# 7_RK3588_DDR_Controler.net
KiCad netlist of a schematic drawn in Altium Designer
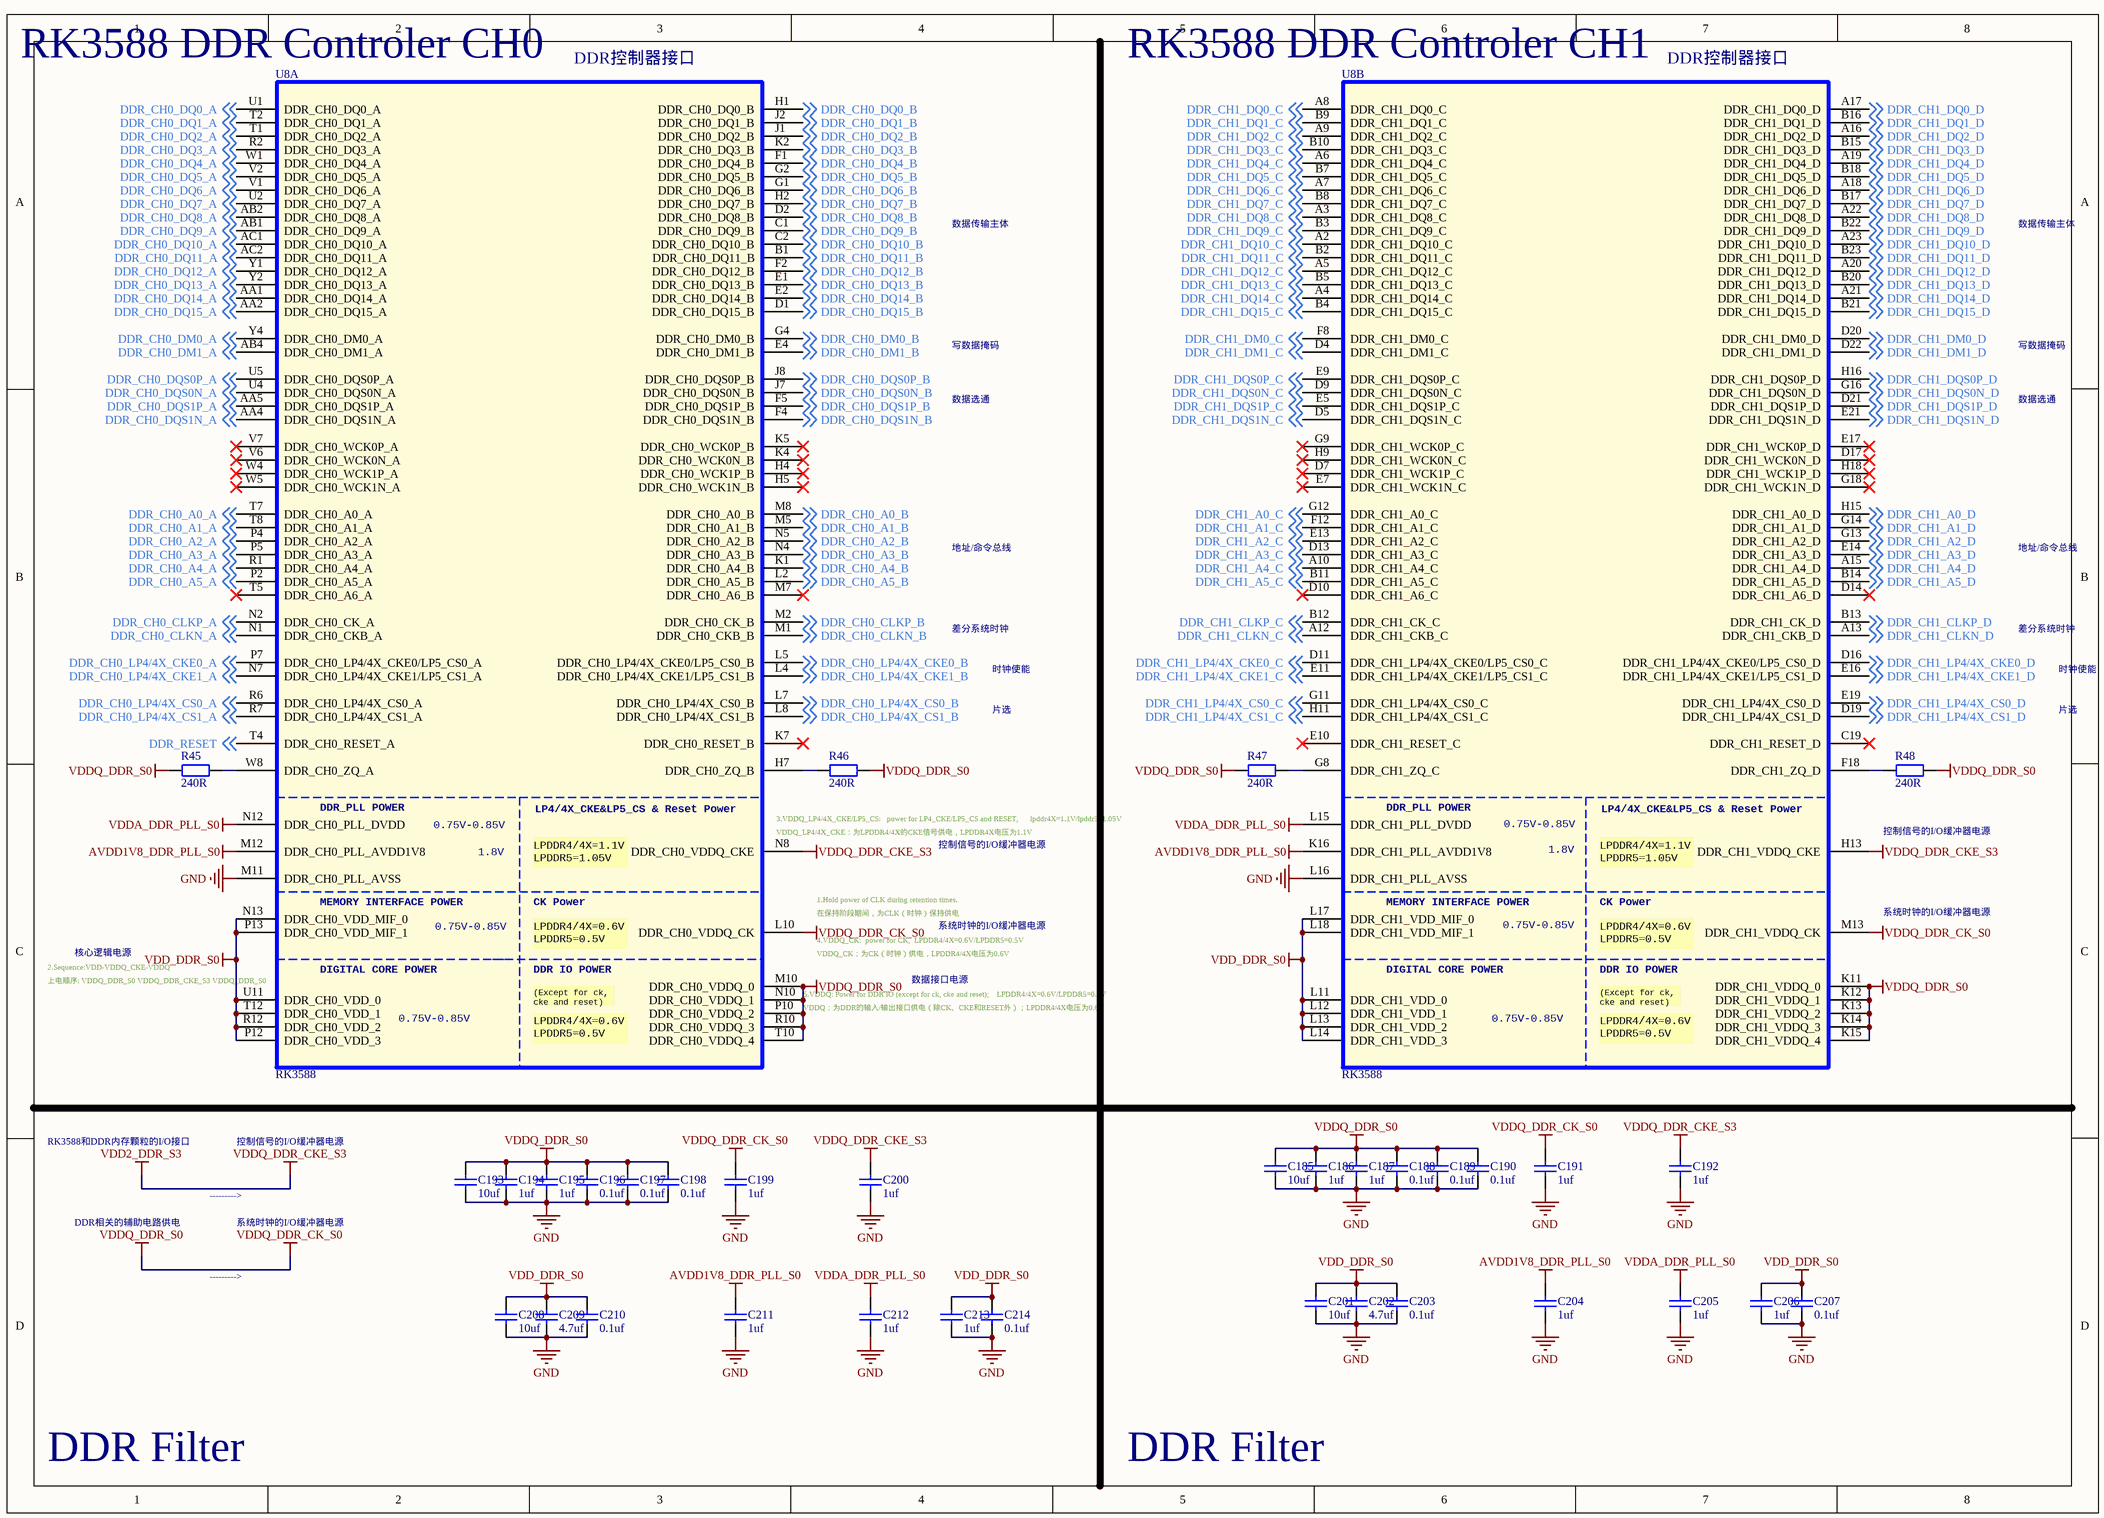
[diagram p0: 7.RK3588_DDR_Controler.SchDoc]

(export (version "E")
  (design (tool "Eeschema 10.0.6"))
  (components
    (comp (ref "C185")
      (value "10uf")
      (footprint "0.PCB1:C0402_L")
      (description "贴片电容/MLCC电容")
      (libsource (lib "RK3588") (part "C"))
    )
    (comp (ref "C186")
      (value "1uf")
      (footprint "0.PCB1:C0201_L")
      (description "贴片电容/MLCC电容")
      (libsource (lib "RK3588") (part "C"))
    )
    (comp (ref "C187")
      (value "1uf")
      (footprint "0.PCB1:C0201_L")
      (description "贴片电容/MLCC电容")
      (libsource (lib "RK3588") (part "C"))
    )
    (comp (ref "C188")
      (value "0.1uf")
      (footprint "0.PCB1:C0201_L")
      (description "贴片电容/MLCC电容")
      (libsource (lib "RK3588") (part "C"))
    )
    (comp (ref "C189")
      (value "0.1uf")
      (footprint "0.PCB1:C0201_L")
      (description "贴片电容/MLCC电容")
      (libsource (lib "RK3588") (part "C"))
    )
    (comp (ref "C190")
      (value "0.1uf")
      (footprint "0.PCB1:C0201_L")
      (description "贴片电容/MLCC电容")
      (libsource (lib "RK3588") (part "C"))
    )
    (comp (ref "C191")
      (value "1uf")
      (footprint "0.PCB1:C0201_L")
      (description "贴片电容/MLCC电容")
      (libsource (lib "RK3588") (part "C"))
    )
    (comp (ref "C192")
      (value "1uf")
      (footprint "0.PCB1:C0201_L")
      (description "贴片电容/MLCC电容")
      (libsource (lib "RK3588") (part "C"))
    )
    (comp (ref "C193")
      (value "10uf")
      (footprint "0.PCB1:C0402_L")
      (description "贴片电容/MLCC电容")
      (libsource (lib "RK3588") (part "C"))
    )
    (comp (ref "C194")
      (value "1uf")
      (footprint "0.PCB1:C0201_L")
      (description "贴片电容/MLCC电容")
      (libsource (lib "RK3588") (part "C"))
    )
    (comp (ref "C195")
      (value "1uf")
      (footprint "0.PCB1:C0201_L")
      (description "贴片电容/MLCC电容")
      (libsource (lib "RK3588") (part "C"))
    )
    (comp (ref "C196")
      (value "0.1uf")
      (footprint "0.PCB1:C0201_L")
      (description "贴片电容/MLCC电容")
      (libsource (lib "RK3588") (part "C"))
    )
    (comp (ref "C197")
      (value "0.1uf")
      (footprint "0.PCB1:C0201_L")
      (description "贴片电容/MLCC电容")
      (libsource (lib "RK3588") (part "C"))
    )
    (comp (ref "C198")
      (value "0.1uf")
      (footprint "0.PCB1:C0201_L")
      (description "贴片电容/MLCC电容")
      (libsource (lib "RK3588") (part "C"))
    )
    (comp (ref "C199")
      (value "1uf")
      (footprint "0.PCB1:C0201_L")
      (description "贴片电容/MLCC电容")
      (libsource (lib "RK3588") (part "C"))
    )
    (comp (ref "C200")
      (value "1uf")
      (footprint "0.PCB1:C0201_L")
      (description "贴片电容/MLCC电容")
      (libsource (lib "RK3588") (part "C"))
    )
    (comp (ref "C201")
      (value "10uf")
      (footprint "0.PCB1:C0402_L")
      (description "贴片电容/MLCC电容")
      (libsource (lib "RK3588") (part "C"))
    )
    (comp (ref "C202")
      (value "4.7uf")
      (footprint "0.PCB1:C0201_L")
      (description "贴片电容/MLCC电容")
      (libsource (lib "RK3588") (part "C"))
    )
    (comp (ref "C203")
      (value "0.1uf")
      (footprint "0.PCB1:C0201_L")
      (description "贴片电容/MLCC电容")
      (libsource (lib "RK3588") (part "C"))
    )
    (comp (ref "C204")
      (value "1uf")
      (footprint "0.PCB1:C0201_L")
      (description "贴片电容/MLCC电容")
      (libsource (lib "RK3588") (part "C"))
    )
    (comp (ref "C205")
      (value "1uf")
      (footprint "0.PCB1:C0201_L")
      (description "贴片电容/MLCC电容")
      (libsource (lib "RK3588") (part "C"))
    )
    (comp (ref "C206")
      (value "1uf")
      (footprint "0.PCB1:C0201_L")
      (description "贴片电容/MLCC电容")
      (libsource (lib "RK3588") (part "C"))
    )
    (comp (ref "C207")
      (value "0.1uf")
      (footprint "0.PCB1:C0201_L")
      (description "贴片电容/MLCC电容")
      (libsource (lib "RK3588") (part "C"))
    )
    (comp (ref "C208")
      (value "10uf")
      (footprint "0.PCB1:C0201_L")
      (description "贴片电容/MLCC电容")
      (libsource (lib "RK3588") (part "C"))
    )
    (comp (ref "C209")
      (value "4.7uf")
      (footprint "0.PCB1:C0201_L")
      (description "贴片电容/MLCC电容")
      (libsource (lib "RK3588") (part "C"))
    )
    (comp (ref "C210")
      (value "0.1uf")
      (footprint "0.PCB1:C0201_L")
      (description "贴片电容/MLCC电容")
      (libsource (lib "RK3588") (part "C"))
    )
    (comp (ref "C211")
      (value "1uf")
      (footprint "0.PCB1:C0201_L")
      (description "贴片电容/MLCC电容")
      (libsource (lib "RK3588") (part "C"))
    )
    (comp (ref "C212")
      (value "1uf")
      (footprint "0.PCB1:C0201_L")
      (description "贴片电容/MLCC电容")
      (libsource (lib "RK3588") (part "C"))
    )
    (comp (ref "C213")
      (value "1uf")
      (footprint "0.PCB1:C0201_L")
      (description "贴片电容/MLCC电容")
      (libsource (lib "RK3588") (part "C"))
    )
    (comp (ref "C214")
      (value "0.1uf")
      (footprint "0.PCB1:C0201_L")
      (description "贴片电容/MLCC电容")
      (libsource (lib "RK3588") (part "C"))
    )
    (comp (ref "R45")
      (value "240R")
      (footprint "0.PCB1:R0201_L")
      (description "贴片电阻")
      (libsource (lib "RK3588") (part "R"))
    )
    (comp (ref "R46")
      (value "240R")
      (footprint "0.PCB1:R0201_L")
      (description "贴片电阻")
      (libsource (lib "RK3588") (part "R"))
    )
    (comp (ref "R47")
      (value "240R")
      (footprint "0.PCB1:R0201_L")
      (description "贴片电阻")
      (libsource (lib "RK3588") (part "R"))
    )
    (comp (ref "R48")
      (value "240R")
      (footprint "0.PCB1:R0201_L")
      (description "贴片电阻")
      (libsource (lib "RK3588") (part "R"))
    )
    (comp (ref "U8")
      (value "RK3588")
      (footprint "0.PCB1:BGA1088_23R00X23R00X2R00")
      (description "ROCKCHIP SOC")
      (libsource (lib "RK3588") (part "SOC_RK3588"))
    )
  )
  (nets
    (net (code "1") (name "AVDD1V8_DDR_PLL_S0") (class "Default")
      (node (ref "C204") (pin "2") (pinfunction "2_2") (pintype "passive"))
      (node (ref "C211") (pin "2") (pinfunction "2_2") (pintype "passive"))
      (node (ref "U8") (pin "K16") (pinfunction "DDR_CH1_PLL_AVDD1V8_K16") (pintype "power_in"))
      (node (ref "U8") (pin "M12") (pinfunction "DDR_CH0_PLL_AVDD1V8_M12") (pintype "power_in"))
    )
    (net (code "2") (name "DDR_CH0_A0_A") (class "Default")
      (node (ref "U8") (pin "T7") (pinfunction "DDR_CH0_A0_A_T7") (pintype "passive"))
    )
    (net (code "3") (name "DDR_CH0_A0_B") (class "Default")
      (node (ref "U8") (pin "M8") (pinfunction "DDR_CH0_A0_B_M8") (pintype "passive"))
    )
    (net (code "4") (name "DDR_CH0_A1_A") (class "Default")
      (node (ref "U8") (pin "T8") (pinfunction "DDR_CH0_A1_A_T8") (pintype "passive"))
    )
    (net (code "5") (name "DDR_CH0_A1_B") (class "Default")
      (node (ref "U8") (pin "M5") (pinfunction "DDR_CH0_A1_B_M5") (pintype "passive"))
    )
    (net (code "6") (name "DDR_CH0_A2_A") (class "Default")
      (node (ref "U8") (pin "P4") (pinfunction "DDR_CH0_A2_A_P4") (pintype "passive"))
    )
    (net (code "7") (name "DDR_CH0_A2_B") (class "Default")
      (node (ref "U8") (pin "N5") (pinfunction "DDR_CH0_A2_B_N5") (pintype "passive"))
    )
    (net (code "8") (name "DDR_CH0_A3_A") (class "Default")
      (node (ref "U8") (pin "P5") (pinfunction "DDR_CH0_A3_A_P5") (pintype "passive"))
    )
    (net (code "9") (name "DDR_CH0_A3_B") (class "Default")
      (node (ref "U8") (pin "N4") (pinfunction "DDR_CH0_A3_B_N4") (pintype "passive"))
    )
    (net (code "10") (name "DDR_CH0_A4_A") (class "Default")
      (node (ref "U8") (pin "R1") (pinfunction "DDR_CH0_A4_A_R1") (pintype "passive"))
    )
    (net (code "11") (name "DDR_CH0_A4_B") (class "Default")
      (node (ref "U8") (pin "K1") (pinfunction "DDR_CH0_A4_B_K1") (pintype "passive"))
    )
    (net (code "12") (name "DDR_CH0_A5_A") (class "Default")
      (node (ref "U8") (pin "P2") (pinfunction "DDR_CH0_A5_A_P2") (pintype "passive"))
    )
    (net (code "13") (name "DDR_CH0_A5_B") (class "Default")
      (node (ref "U8") (pin "L2") (pinfunction "DDR_CH0_A5_B_L2") (pintype "passive"))
    )
    (net (code "14") (name "DDR_CH0_CLKN_A") (class "Default")
      (node (ref "U8") (pin "N1") (pinfunction "DDR_CH0_CKB_A_N1") (pintype "passive"))
    )
    (net (code "15") (name "DDR_CH0_CLKN_B") (class "Default")
      (node (ref "U8") (pin "M1") (pinfunction "DDR_CH0_CKB_B_M1") (pintype "passive"))
    )
    (net (code "16") (name "DDR_CH0_CLKP_A") (class "Default")
      (node (ref "U8") (pin "N2") (pinfunction "DDR_CH0_CK_A_N2") (pintype "passive"))
    )
    (net (code "17") (name "DDR_CH0_CLKP_B") (class "Default")
      (node (ref "U8") (pin "M2") (pinfunction "DDR_CH0_CK_B_M2") (pintype "passive"))
    )
    (net (code "18") (name "DDR_CH0_DM0_A") (class "Default")
      (node (ref "U8") (pin "Y4") (pinfunction "DDR_CH0_DM0_A_Y4") (pintype "passive"))
    )
    (net (code "19") (name "DDR_CH0_DM0_B") (class "Default")
      (node (ref "U8") (pin "G4") (pinfunction "DDR_CH0_DM0_B_G4") (pintype "passive"))
    )
    (net (code "20") (name "DDR_CH0_DM1_A") (class "Default")
      (node (ref "U8") (pin "AB4") (pinfunction "DDR_CH0_DM1_A_AB4") (pintype "passive"))
    )
    (net (code "21") (name "DDR_CH0_DM1_B") (class "Default")
      (node (ref "U8") (pin "E4") (pinfunction "DDR_CH0_DM1_B_E4") (pintype "passive"))
    )
    (net (code "22") (name "DDR_CH0_DQ0_A") (class "Default")
      (node (ref "U8") (pin "U1") (pinfunction "DDR_CH0_DQ0_A_U1") (pintype "passive"))
    )
    (net (code "23") (name "DDR_CH0_DQ0_B") (class "Default")
      (node (ref "U8") (pin "H1") (pinfunction "DDR_CH0_DQ0_B_H1") (pintype "passive"))
    )
    (net (code "24") (name "DDR_CH0_DQ1_A") (class "Default")
      (node (ref "U8") (pin "T2") (pinfunction "DDR_CH0_DQ1_A_T2") (pintype "passive"))
    )
    (net (code "25") (name "DDR_CH0_DQ1_B") (class "Default")
      (node (ref "U8") (pin "J2") (pinfunction "DDR_CH0_DQ1_B_J2") (pintype "passive"))
    )
    (net (code "26") (name "DDR_CH0_DQ2_A") (class "Default")
      (node (ref "U8") (pin "T1") (pinfunction "DDR_CH0_DQ2_A_T1") (pintype "passive"))
    )
    (net (code "27") (name "DDR_CH0_DQ2_B") (class "Default")
      (node (ref "U8") (pin "J1") (pinfunction "DDR_CH0_DQ2_B_J1") (pintype "passive"))
    )
    (net (code "28") (name "DDR_CH0_DQ3_A") (class "Default")
      (node (ref "U8") (pin "R2") (pinfunction "DDR_CH0_DQ3_A_R2") (pintype "passive"))
    )
    (net (code "29") (name "DDR_CH0_DQ3_B") (class "Default")
      (node (ref "U8") (pin "K2") (pinfunction "DDR_CH0_DQ3_B_K2") (pintype "passive"))
    )
    (net (code "30") (name "DDR_CH0_DQ4_A") (class "Default")
      (node (ref "U8") (pin "W1") (pinfunction "DDR_CH0_DQ4_A_W1") (pintype "passive"))
    )
    (net (code "31") (name "DDR_CH0_DQ4_B") (class "Default")
      (node (ref "U8") (pin "F1") (pinfunction "DDR_CH0_DQ4_B_F1") (pintype "passive"))
    )
    (net (code "32") (name "DDR_CH0_DQ5_A") (class "Default")
      (node (ref "U8") (pin "V2") (pinfunction "DDR_CH0_DQ5_A_V2") (pintype "passive"))
    )
    (net (code "33") (name "DDR_CH0_DQ5_B") (class "Default")
      (node (ref "U8") (pin "G2") (pinfunction "DDR_CH0_DQ5_B_G2") (pintype "passive"))
    )
    (net (code "34") (name "DDR_CH0_DQ6_A") (class "Default")
      (node (ref "U8") (pin "V1") (pinfunction "DDR_CH0_DQ6_A_V1") (pintype "passive"))
    )
    (net (code "35") (name "DDR_CH0_DQ6_B") (class "Default")
      (node (ref "U8") (pin "G1") (pinfunction "DDR_CH0_DQ6_B_G1") (pintype "passive"))
    )
    (net (code "36") (name "DDR_CH0_DQ7_A") (class "Default")
      (node (ref "U8") (pin "U2") (pinfunction "DDR_CH0_DQ7_A_U2") (pintype "passive"))
    )
    (net (code "37") (name "DDR_CH0_DQ7_B") (class "Default")
      (node (ref "U8") (pin "H2") (pinfunction "DDR_CH0_DQ7_B_H2") (pintype "passive"))
    )
    (net (code "38") (name "DDR_CH0_DQ8_A") (class "Default")
      (node (ref "U8") (pin "AB2") (pinfunction "DDR_CH0_DQ8_A_AB2") (pintype "passive"))
    )
    (net (code "39") (name "DDR_CH0_DQ8_B") (class "Default")
      (node (ref "U8") (pin "D2") (pinfunction "DDR_CH0_DQ8_B_D2") (pintype "passive"))
    )
    (net (code "40") (name "DDR_CH0_DQ9_A") (class "Default")
      (node (ref "U8") (pin "AB1") (pinfunction "DDR_CH0_DQ9_A_AB1") (pintype "passive"))
    )
    (net (code "41") (name "DDR_CH0_DQ9_B") (class "Default")
      (node (ref "U8") (pin "C1") (pinfunction "DDR_CH0_DQ9_B_C1") (pintype "passive"))
    )
    (net (code "42") (name "DDR_CH0_DQ10_A") (class "Default")
      (node (ref "U8") (pin "AC1") (pinfunction "DDR_CH0_DQ10_A_AC1") (pintype "passive"))
    )
    (net (code "43") (name "DDR_CH0_DQ10_B") (class "Default")
      (node (ref "U8") (pin "C2") (pinfunction "DDR_CH0_DQ10_B_C2") (pintype "passive"))
    )
    (net (code "44") (name "DDR_CH0_DQ11_A") (class "Default")
      (node (ref "U8") (pin "AC2") (pinfunction "DDR_CH0_DQ11_A_AC2") (pintype "passive"))
    )
    (net (code "45") (name "DDR_CH0_DQ11_B") (class "Default")
      (node (ref "U8") (pin "B1") (pinfunction "DDR_CH0_DQ11_B_B1") (pintype "passive"))
    )
    (net (code "46") (name "DDR_CH0_DQ12_A") (class "Default")
      (node (ref "U8") (pin "Y1") (pinfunction "DDR_CH0_DQ12_A_Y1") (pintype "passive"))
    )
    (net (code "47") (name "DDR_CH0_DQ12_B") (class "Default")
      (node (ref "U8") (pin "F2") (pinfunction "DDR_CH0_DQ12_B_F2") (pintype "passive"))
    )
    (net (code "48") (name "DDR_CH0_DQ13_A") (class "Default")
      (node (ref "U8") (pin "Y2") (pinfunction "DDR_CH0_DQ13_A_Y2") (pintype "passive"))
    )
    (net (code "49") (name "DDR_CH0_DQ13_B") (class "Default")
      (node (ref "U8") (pin "E1") (pinfunction "DDR_CH0_DQ13_B_E1") (pintype "passive"))
    )
    (net (code "50") (name "DDR_CH0_DQ14_A") (class "Default")
      (node (ref "U8") (pin "AA1") (pinfunction "DDR_CH0_DQ14_A_AA1") (pintype "passive"))
    )
    (net (code "51") (name "DDR_CH0_DQ14_B") (class "Default")
      (node (ref "U8") (pin "E2") (pinfunction "DDR_CH0_DQ14_B_E2") (pintype "passive"))
    )
    (net (code "52") (name "DDR_CH0_DQ15_A") (class "Default")
      (node (ref "U8") (pin "AA2") (pinfunction "DDR_CH0_DQ15_A_AA2") (pintype "passive"))
    )
    (net (code "53") (name "DDR_CH0_DQ15_B") (class "Default")
      (node (ref "U8") (pin "D1") (pinfunction "DDR_CH0_DQ15_B_D1") (pintype "passive"))
    )
    (net (code "54") (name "DDR_CH0_DQS0N_A") (class "Default")
      (node (ref "U8") (pin "U4") (pinfunction "DDR_CH0_DQS0N_A_U4") (pintype "passive"))
    )
    (net (code "55") (name "DDR_CH0_DQS0N_B") (class "Default")
      (node (ref "U8") (pin "J7") (pinfunction "DDR_CH0_DQS0N_B_J7") (pintype "passive"))
    )
    (net (code "56") (name "DDR_CH0_DQS0P_A") (class "Default")
      (node (ref "U8") (pin "U5") (pinfunction "DDR_CH0_DQS0P_A_U5") (pintype "passive"))
    )
    (net (code "57") (name "DDR_CH0_DQS0P_B") (class "Default")
      (node (ref "U8") (pin "J8") (pinfunction "DDR_CH0_DQS0P_B_J8") (pintype "passive"))
    )
    (net (code "58") (name "DDR_CH0_DQS1N_A") (class "Default")
      (node (ref "U8") (pin "AA4") (pinfunction "DDR_CH0_DQS1N_A_AA4") (pintype "passive"))
    )
    (net (code "59") (name "DDR_CH0_DQS1N_B") (class "Default")
      (node (ref "U8") (pin "F4") (pinfunction "DDR_CH0_DQS1N_B_F4") (pintype "passive"))
    )
    (net (code "60") (name "DDR_CH0_DQS1P_A") (class "Default")
      (node (ref "U8") (pin "AA5") (pinfunction "DDR_CH0_DQS1P_A_AA5") (pintype "passive"))
    )
    (net (code "61") (name "DDR_CH0_DQS1P_B") (class "Default")
      (node (ref "U8") (pin "F5") (pinfunction "DDR_CH0_DQS1P_B_F5") (pintype "passive"))
    )
    (net (code "62") (name "DDR_CH0_LP4{slash}4X_CKE0_A") (class "Default")
      (node (ref "U8") (pin "P7") (pinfunction "DDR_CH0_LP4/4X_CKE0/LP5_CS0_A_P7") (pintype "passive"))
    )
    (net (code "63") (name "DDR_CH0_LP4{slash}4X_CKE0_B") (class "Default")
      (node (ref "U8") (pin "L5") (pinfunction "DDR_CH0_LP4/4X_CKE0/LP5_CS0_B_L5") (pintype "passive"))
    )
    (net (code "64") (name "DDR_CH0_LP4{slash}4X_CKE1_A") (class "Default")
      (node (ref "U8") (pin "N7") (pinfunction "DDR_CH0_LP4/4X_CKE1/LP5_CS1_A_N7") (pintype "passive"))
    )
    (net (code "65") (name "DDR_CH0_LP4{slash}4X_CKE1_B") (class "Default")
      (node (ref "U8") (pin "L4") (pinfunction "DDR_CH0_LP4/4X_CKE1/LP5_CS1_B_L4") (pintype "passive"))
    )
    (net (code "66") (name "DDR_CH0_LP4{slash}4X_CS0_A") (class "Default")
      (node (ref "U8") (pin "R6") (pinfunction "DDR_CH0_LP4/4X_CS0_A_R6") (pintype "passive"))
    )
    (net (code "67") (name "DDR_CH0_LP4{slash}4X_CS0_B") (class "Default")
      (node (ref "U8") (pin "L7") (pinfunction "DDR_CH0_LP4/4X_CS0_B_L7") (pintype "passive"))
    )
    (net (code "68") (name "DDR_CH0_LP4{slash}4X_CS1_A") (class "Default")
      (node (ref "U8") (pin "R7") (pinfunction "DDR_CH0_LP4/4X_CS1_A_R7") (pintype "passive"))
    )
    (net (code "69") (name "DDR_CH0_LP4{slash}4X_CS1_B") (class "Default")
      (node (ref "U8") (pin "L8") (pinfunction "DDR_CH0_LP4/4X_CS1_B_L8") (pintype "passive"))
    )
    (net (code "70") (name "DDR_CH1_A0_C") (class "Default")
      (node (ref "U8") (pin "G12") (pinfunction "DDR_CH1_A0_C_G12") (pintype "passive"))
    )
    (net (code "71") (name "DDR_CH1_A0_D") (class "Default")
      (node (ref "U8") (pin "H15") (pinfunction "DDR_CH1_A0_D_H15") (pintype "passive"))
    )
    (net (code "72") (name "DDR_CH1_A1_C") (class "Default")
      (node (ref "U8") (pin "F12") (pinfunction "DDR_CH1_A1_C_F12") (pintype "passive"))
    )
    (net (code "73") (name "DDR_CH1_A1_D") (class "Default")
      (node (ref "U8") (pin "G14") (pinfunction "DDR_CH1_A1_D_G14") (pintype "passive"))
    )
    (net (code "74") (name "DDR_CH1_A2_C") (class "Default")
      (node (ref "U8") (pin "E13") (pinfunction "DDR_CH1_A2_C_E13") (pintype "passive"))
    )
    (net (code "75") (name "DDR_CH1_A2_D") (class "Default")
      (node (ref "U8") (pin "G13") (pinfunction "DDR_CH1_A2_D_G13") (pintype "passive"))
    )
    (net (code "76") (name "DDR_CH1_A3_C") (class "Default")
      (node (ref "U8") (pin "D13") (pinfunction "DDR_CH1_A3_C_D13") (pintype "passive"))
    )
    (net (code "77") (name "DDR_CH1_A3_D") (class "Default")
      (node (ref "U8") (pin "E14") (pinfunction "DDR_CH1_A3_D_E14") (pintype "passive"))
    )
    (net (code "78") (name "DDR_CH1_A4_C") (class "Default")
      (node (ref "U8") (pin "A10") (pinfunction "DDR_CH1_A4_C_A10") (pintype "passive"))
    )
    (net (code "79") (name "DDR_CH1_A4_D") (class "Default")
      (node (ref "U8") (pin "A15") (pinfunction "DDR_CH1_A4_D_A15") (pintype "passive"))
    )
    (net (code "80") (name "DDR_CH1_A5_C") (class "Default")
      (node (ref "U8") (pin "B11") (pinfunction "DDR_CH1_A5_C_B11") (pintype "passive"))
    )
    (net (code "81") (name "DDR_CH1_A5_D") (class "Default")
      (node (ref "U8") (pin "B14") (pinfunction "DDR_CH1_A5_D_B14") (pintype "passive"))
    )
    (net (code "82") (name "DDR_CH1_CLKN_C") (class "Default")
      (node (ref "U8") (pin "A12") (pinfunction "DDR_CH1_CKB_C_A12") (pintype "passive"))
    )
    (net (code "83") (name "DDR_CH1_CLKN_D") (class "Default")
      (node (ref "U8") (pin "A13") (pinfunction "DDR_CH1_CKB_D_A13") (pintype "passive"))
    )
    (net (code "84") (name "DDR_CH1_CLKP_C") (class "Default")
      (node (ref "U8") (pin "B12") (pinfunction "DDR_CH1_CK_C_B12") (pintype "passive"))
    )
    (net (code "85") (name "DDR_CH1_CLKP_D") (class "Default")
      (node (ref "U8") (pin "B13") (pinfunction "DDR_CH1_CK_D_B13") (pintype "passive"))
    )
    (net (code "86") (name "DDR_CH1_DM0_C") (class "Default")
      (node (ref "U8") (pin "F8") (pinfunction "DDR_CH1_DM0_C_F8") (pintype "passive"))
    )
    (net (code "87") (name "DDR_CH1_DM0_D") (class "Default")
      (node (ref "U8") (pin "D20") (pinfunction "DDR_CH1_DM0_D_D20") (pintype "passive"))
    )
    (net (code "88") (name "DDR_CH1_DM1_C") (class "Default")
      (node (ref "U8") (pin "D4") (pinfunction "DDR_CH1_DM1_C_D4") (pintype "passive"))
    )
    (net (code "89") (name "DDR_CH1_DM1_D") (class "Default")
      (node (ref "U8") (pin "D22") (pinfunction "DDR_CH1_DM1_D_D22") (pintype "passive"))
    )
    (net (code "90") (name "DDR_CH1_DQ0_C") (class "Default")
      (node (ref "U8") (pin "A8") (pinfunction "DDR_CH1_DQ0_C_A8") (pintype "passive"))
    )
    (net (code "91") (name "DDR_CH1_DQ0_D") (class "Default")
      (node (ref "U8") (pin "A17") (pinfunction "DDR_CH1_DQ0_D_A17") (pintype "passive"))
    )
    (net (code "92") (name "DDR_CH1_DQ1_C") (class "Default")
      (node (ref "U8") (pin "B9") (pinfunction "DDR_CH1_DQ1_C_B9") (pintype "passive"))
    )
    (net (code "93") (name "DDR_CH1_DQ1_D") (class "Default")
      (node (ref "U8") (pin "B16") (pinfunction "DDR_CH1_DQ1_D_B16") (pintype "passive"))
    )
    (net (code "94") (name "DDR_CH1_DQ2_C") (class "Default")
      (node (ref "U8") (pin "A9") (pinfunction "DDR_CH1_DQ2_C_A9") (pintype "passive"))
    )
    (net (code "95") (name "DDR_CH1_DQ2_D") (class "Default")
      (node (ref "U8") (pin "A16") (pinfunction "DDR_CH1_DQ2_D_A16") (pintype "passive"))
    )
    (net (code "96") (name "DDR_CH1_DQ3_C") (class "Default")
      (node (ref "U8") (pin "B10") (pinfunction "DDR_CH1_DQ3_C_B10") (pintype "passive"))
    )
    (net (code "97") (name "DDR_CH1_DQ3_D") (class "Default")
      (node (ref "U8") (pin "B15") (pinfunction "DDR_CH1_DQ3_D_B15") (pintype "passive"))
    )
    (net (code "98") (name "DDR_CH1_DQ4_C") (class "Default")
      (node (ref "U8") (pin "A6") (pinfunction "DDR_CH1_DQ4_C_A6") (pintype "passive"))
    )
    (net (code "99") (name "DDR_CH1_DQ4_D") (class "Default")
      (node (ref "U8") (pin "A19") (pinfunction "DDR_CH1_DQ4_D_A19") (pintype "passive"))
    )
    (net (code "100") (name "DDR_CH1_DQ5_C") (class "Default")
      (node (ref "U8") (pin "B7") (pinfunction "DDR_CH1_DQ5_C_B7") (pintype "passive"))
    )
    (net (code "101") (name "DDR_CH1_DQ5_D") (class "Default")
      (node (ref "U8") (pin "B18") (pinfunction "DDR_CH1_DQ5_D_B18") (pintype "passive"))
    )
    (net (code "102") (name "DDR_CH1_DQ6_C") (class "Default")
      (node (ref "U8") (pin "A7") (pinfunction "DDR_CH1_DQ6_C_A7") (pintype "passive"))
    )
    (net (code "103") (name "DDR_CH1_DQ6_D") (class "Default")
      (node (ref "U8") (pin "A18") (pinfunction "DDR_CH1_DQ6_D_A18") (pintype "passive"))
    )
    (net (code "104") (name "DDR_CH1_DQ7_C") (class "Default")
      (node (ref "U8") (pin "B8") (pinfunction "DDR_CH1_DQ7_C_B8") (pintype "passive"))
    )
    (net (code "105") (name "DDR_CH1_DQ7_D") (class "Default")
      (node (ref "U8") (pin "B17") (pinfunction "DDR_CH1_DQ7_D_B17") (pintype "passive"))
    )
    (net (code "106") (name "DDR_CH1_DQ8_C") (class "Default")
      (node (ref "U8") (pin "A3") (pinfunction "DDR_CH1_DQ8_C_A3") (pintype "passive"))
    )
    (net (code "107") (name "DDR_CH1_DQ8_D") (class "Default")
      (node (ref "U8") (pin "A22") (pinfunction "DDR_CH1_DQ8_D_A22") (pintype "passive"))
    )
    (net (code "108") (name "DDR_CH1_DQ9_C") (class "Default")
      (node (ref "U8") (pin "B3") (pinfunction "DDR_CH1_DQ9_C_B3") (pintype "passive"))
    )
    (net (code "109") (name "DDR_CH1_DQ9_D") (class "Default")
      (node (ref "U8") (pin "B22") (pinfunction "DDR_CH1_DQ9_D_B22") (pintype "passive"))
    )
    (net (code "110") (name "DDR_CH1_DQ10_C") (class "Default")
      (node (ref "U8") (pin "A2") (pinfunction "DDR_CH1_DQ10_C_A2") (pintype "passive"))
    )
    (net (code "111") (name "DDR_CH1_DQ10_D") (class "Default")
      (node (ref "U8") (pin "A23") (pinfunction "DDR_CH1_DQ10_D_A23") (pintype "passive"))
    )
    (net (code "112") (name "DDR_CH1_DQ11_C") (class "Default")
      (node (ref "U8") (pin "B2") (pinfunction "DDR_CH1_DQ11_C_B2") (pintype "passive"))
    )
    (net (code "113") (name "DDR_CH1_DQ11_D") (class "Default")
      (node (ref "U8") (pin "B23") (pinfunction "DDR_CH1_DQ11_D_B23") (pintype "passive"))
    )
    (net (code "114") (name "DDR_CH1_DQ12_C") (class "Default")
      (node (ref "U8") (pin "A5") (pinfunction "DDR_CH1_DQ12_C_A5") (pintype "passive"))
    )
    (net (code "115") (name "DDR_CH1_DQ12_D") (class "Default")
      (node (ref "U8") (pin "A20") (pinfunction "DDR_CH1_DQ12_D_A20") (pintype "passive"))
    )
    (net (code "116") (name "DDR_CH1_DQ13_C") (class "Default")
      (node (ref "U8") (pin "B5") (pinfunction "DDR_CH1_DQ13_C_B5") (pintype "passive"))
    )
    (net (code "117") (name "DDR_CH1_DQ13_D") (class "Default")
      (node (ref "U8") (pin "B20") (pinfunction "DDR_CH1_DQ13_D_B20") (pintype "passive"))
    )
    (net (code "118") (name "DDR_CH1_DQ14_C") (class "Default")
      (node (ref "U8") (pin "A4") (pinfunction "DDR_CH1_DQ14_C_A4") (pintype "passive"))
    )
    (net (code "119") (name "DDR_CH1_DQ14_D") (class "Default")
      (node (ref "U8") (pin "A21") (pinfunction "DDR_CH1_DQ14_D_A21") (pintype "passive"))
    )
    (net (code "120") (name "DDR_CH1_DQ15_C") (class "Default")
      (node (ref "U8") (pin "B4") (pinfunction "DDR_CH1_DQ15_C_B4") (pintype "passive"))
    )
    (net (code "121") (name "DDR_CH1_DQ15_D") (class "Default")
      (node (ref "U8") (pin "B21") (pinfunction "DDR_CH1_DQ15_D_B21") (pintype "passive"))
    )
    (net (code "122") (name "DDR_CH1_DQS0N_C") (class "Default")
      (node (ref "U8") (pin "D9") (pinfunction "DDR_CH1_DQS0N_C_D9") (pintype "passive"))
    )
    (net (code "123") (name "DDR_CH1_DQS0N_D") (class "Default")
      (node (ref "U8") (pin "G16") (pinfunction "DDR_CH1_DQS0N_D_G16") (pintype "passive"))
    )
    (net (code "124") (name "DDR_CH1_DQS0P_C") (class "Default")
      (node (ref "U8") (pin "E9") (pinfunction "DDR_CH1_DQS0P_C_E9") (pintype "passive"))
    )
    (net (code "125") (name "DDR_CH1_DQS0P_D") (class "Default")
      (node (ref "U8") (pin "H16") (pinfunction "DDR_CH1_DQS0P_D_H16") (pintype "passive"))
    )
    (net (code "126") (name "DDR_CH1_DQS1N_C") (class "Default")
      (node (ref "U8") (pin "D5") (pinfunction "DDR_CH1_DQS1N_C_D5") (pintype "passive"))
    )
    (net (code "127") (name "DDR_CH1_DQS1N_D") (class "Default")
      (node (ref "U8") (pin "E21") (pinfunction "DDR_CH1_DQS1N_D_E21") (pintype "passive"))
    )
    (net (code "128") (name "DDR_CH1_DQS1P_C") (class "Default")
      (node (ref "U8") (pin "E5") (pinfunction "DDR_CH1_DQS1P_C_E5") (pintype "passive"))
    )
    (net (code "129") (name "DDR_CH1_DQS1P_D") (class "Default")
      (node (ref "U8") (pin "D21") (pinfunction "DDR_CH1_DQS1P_D_D21") (pintype "passive"))
    )
    (net (code "130") (name "DDR_CH1_LP4{slash}4X_CKE0_C") (class "Default")
      (node (ref "U8") (pin "D11") (pinfunction "DDR_CH1_LP4/4X_CKE0/LP5_CS0_C_D11") (pintype "passive"))
    )
    (net (code "131") (name "DDR_CH1_LP4{slash}4X_CKE0_D") (class "Default")
      (node (ref "U8") (pin "D16") (pinfunction "DDR_CH1_LP4/4X_CKE0/LP5_CS0_D_D16") (pintype "passive"))
    )
    (net (code "132") (name "DDR_CH1_LP4{slash}4X_CKE1_C") (class "Default")
      (node (ref "U8") (pin "E11") (pinfunction "DDR_CH1_LP4/4X_CKE1/LP5_CS1_C_E11") (pintype "passive"))
    )
    (net (code "133") (name "DDR_CH1_LP4{slash}4X_CKE1_D") (class "Default")
      (node (ref "U8") (pin "E16") (pinfunction "DDR_CH1_LP4/4X_CKE1/LP5_CS1_D_E16") (pintype "passive"))
    )
    (net (code "134") (name "DDR_CH1_LP4{slash}4X_CS0_C") (class "Default")
      (node (ref "U8") (pin "G11") (pinfunction "DDR_CH1_LP4/4X_CS0_C_G11") (pintype "passive"))
    )
    (net (code "135") (name "DDR_CH1_LP4{slash}4X_CS0_D") (class "Default")
      (node (ref "U8") (pin "E19") (pinfunction "DDR_CH1_LP4/4X_CS0_D_E19") (pintype "passive"))
    )
    (net (code "136") (name "DDR_CH1_LP4{slash}4X_CS1_C") (class "Default")
      (node (ref "U8") (pin "H11") (pinfunction "DDR_CH1_LP4/4X_CS1_C_H11") (pintype "passive"))
    )
    (net (code "137") (name "DDR_CH1_LP4{slash}4X_CS1_D") (class "Default")
      (node (ref "U8") (pin "D19") (pinfunction "DDR_CH1_LP4/4X_CS1_D_D19") (pintype "passive"))
    )
    (net (code "138") (name "DDR_RESET") (class "Default")
      (node (ref "U8") (pin "T4") (pinfunction "DDR_CH0_RESET_A_T4") (pintype "passive"))
    )
    (net (code "139") (name "GND") (class "Default")
      (node (ref "C185") (pin "1") (pinfunction "1_1") (pintype "passive"))
      (node (ref "C186") (pin "1") (pinfunction "1_1") (pintype "passive"))
      (node (ref "C187") (pin "1") (pinfunction "1_1") (pintype "passive"))
      (node (ref "C188") (pin "1") (pinfunction "1_1") (pintype "passive"))
      (node (ref "C189") (pin "1") (pinfunction "1_1") (pintype "passive"))
      (node (ref "C190") (pin "1") (pinfunction "1_1") (pintype "passive"))
      (node (ref "C191") (pin "1") (pinfunction "1_1") (pintype "passive"))
      (node (ref "C192") (pin "1") (pinfunction "1_1") (pintype "passive"))
      (node (ref "C193") (pin "1") (pinfunction "1_1") (pintype "passive"))
      (node (ref "C194") (pin "1") (pinfunction "1_1") (pintype "passive"))
      (node (ref "C195") (pin "1") (pinfunction "1_1") (pintype "passive"))
      (node (ref "C196") (pin "1") (pinfunction "1_1") (pintype "passive"))
      (node (ref "C197") (pin "1") (pinfunction "1_1") (pintype "passive"))
      (node (ref "C198") (pin "1") (pinfunction "1_1") (pintype "passive"))
      (node (ref "C199") (pin "1") (pinfunction "1_1") (pintype "passive"))
      (node (ref "C200") (pin "1") (pinfunction "1_1") (pintype "passive"))
      (node (ref "C201") (pin "1") (pinfunction "1_1") (pintype "passive"))
      (node (ref "C202") (pin "1") (pinfunction "1_1") (pintype "passive"))
      (node (ref "C203") (pin "1") (pinfunction "1_1") (pintype "passive"))
      (node (ref "C204") (pin "1") (pinfunction "1_1") (pintype "passive"))
      (node (ref "C205") (pin "1") (pinfunction "1_1") (pintype "passive"))
      (node (ref "C206") (pin "1") (pinfunction "1_1") (pintype "passive"))
      (node (ref "C207") (pin "1") (pinfunction "1_1") (pintype "passive"))
      (node (ref "C208") (pin "1") (pinfunction "1_1") (pintype "passive"))
      (node (ref "C209") (pin "1") (pinfunction "1_1") (pintype "passive"))
      (node (ref "C210") (pin "1") (pinfunction "1_1") (pintype "passive"))
      (node (ref "C211") (pin "1") (pinfunction "1_1") (pintype "passive"))
      (node (ref "C212") (pin "1") (pinfunction "1_1") (pintype "passive"))
      (node (ref "C213") (pin "1") (pinfunction "1_1") (pintype "passive"))
      (node (ref "C214") (pin "1") (pinfunction "1_1") (pintype "passive"))
      (node (ref "U8") (pin "L16") (pinfunction "DDR_CH1_PLL_AVSS_L16") (pintype "power_in"))
      (node (ref "U8") (pin "M11") (pinfunction "DDR_CH0_PLL_AVSS_M11") (pintype "power_in"))
    )
    (net (code "140") (name "Net-(U8A-DDR_CH0_ZQ_A)") (class "Default")
      (node (ref "R45") (pin "2") (pinfunction "2_2") (pintype "passive"))
      (node (ref "U8") (pin "W8") (pinfunction "DDR_CH0_ZQ_A_W8") (pintype "passive"))
    )
    (net (code "141") (name "Net-(U8A-DDR_CH0_ZQ_B)") (class "Default")
      (node (ref "R46") (pin "2") (pinfunction "2_2") (pintype "passive"))
      (node (ref "U8") (pin "H7") (pinfunction "DDR_CH0_ZQ_B_H7") (pintype "passive"))
    )
    (net (code "142") (name "Net-(U8B-DDR_CH1_ZQ_C)") (class "Default")
      (node (ref "R47") (pin "2") (pinfunction "2_2") (pintype "passive"))
      (node (ref "U8") (pin "G8") (pinfunction "DDR_CH1_ZQ_C_G8") (pintype "passive"))
    )
    (net (code "143") (name "Net-(U8B-DDR_CH1_ZQ_D)") (class "Default")
      (node (ref "R48") (pin "2") (pinfunction "2_2") (pintype "passive"))
      (node (ref "U8") (pin "F18") (pinfunction "DDR_CH1_ZQ_D_F18") (pintype "passive"))
    )
    (net (code "144") (name "VDD2_DDR_S3") (class "Default")
      (node (ref "C192") (pin "2") (pinfunction "2_2") (pintype "passive"))
      (node (ref "C200") (pin "2") (pinfunction "2_2") (pintype "passive"))
      (node (ref "U8") (pin "H13") (pinfunction "DDR_CH1_VDDQ_CKE_H13") (pintype "power_in"))
      (node (ref "U8") (pin "N8") (pinfunction "DDR_CH0_VDDQ_CKE_N8") (pintype "power_in"))
    )
    (net (code "145") (name "VDDA_DDR_PLL_S0") (class "Default")
      (node (ref "C205") (pin "2") (pinfunction "2_2") (pintype "passive"))
      (node (ref "C212") (pin "2") (pinfunction "2_2") (pintype "passive"))
      (node (ref "U8") (pin "L15") (pinfunction "DDR_CH1_PLL_DVDD_L15") (pintype "power_in"))
      (node (ref "U8") (pin "N12") (pinfunction "DDR_CH0_PLL_DVDD_N12") (pintype "power_in"))
    )
    (net (code "146") (name "VDDQ_DDR_CK_S0") (class "Default")
      (node (ref "C185") (pin "2") (pinfunction "2_2") (pintype "passive"))
      (node (ref "C186") (pin "2") (pinfunction "2_2") (pintype "passive"))
      (node (ref "C187") (pin "2") (pinfunction "2_2") (pintype "passive"))
      (node (ref "C188") (pin "2") (pinfunction "2_2") (pintype "passive"))
      (node (ref "C189") (pin "2") (pinfunction "2_2") (pintype "passive"))
      (node (ref "C190") (pin "2") (pinfunction "2_2") (pintype "passive"))
      (node (ref "C191") (pin "2") (pinfunction "2_2") (pintype "passive"))
      (node (ref "C193") (pin "2") (pinfunction "2_2") (pintype "passive"))
      (node (ref "C194") (pin "2") (pinfunction "2_2") (pintype "passive"))
      (node (ref "C195") (pin "2") (pinfunction "2_2") (pintype "passive"))
      (node (ref "C196") (pin "2") (pinfunction "2_2") (pintype "passive"))
      (node (ref "C197") (pin "2") (pinfunction "2_2") (pintype "passive"))
      (node (ref "C198") (pin "2") (pinfunction "2_2") (pintype "passive"))
      (node (ref "C199") (pin "2") (pinfunction "2_2") (pintype "passive"))
      (node (ref "R45") (pin "1") (pinfunction "1_1") (pintype "passive"))
      (node (ref "R46") (pin "1") (pinfunction "1_1") (pintype "passive"))
      (node (ref "R47") (pin "1") (pinfunction "1_1") (pintype "passive"))
      (node (ref "R48") (pin "1") (pinfunction "1_1") (pintype "passive"))
      (node (ref "U8") (pin "K11") (pinfunction "DDR_CH1_VDDQ_0_K11") (pintype "power_in"))
      (node (ref "U8") (pin "K12") (pinfunction "DDR_CH1_VDDQ_1_K12") (pintype "power_in"))
      (node (ref "U8") (pin "K13") (pinfunction "DDR_CH1_VDDQ_2_K13") (pintype "power_in"))
      (node (ref "U8") (pin "K14") (pinfunction "DDR_CH1_VDDQ_3_K14") (pintype "power_in"))
      (node (ref "U8") (pin "K15") (pinfunction "DDR_CH1_VDDQ_4_K15") (pintype "power_in"))
      (node (ref "U8") (pin "L10") (pinfunction "DDR_CH0_VDDQ_CK_L10") (pintype "power_in"))
      (node (ref "U8") (pin "M10") (pinfunction "DDR_CH0_VDDQ_0_M10") (pintype "power_in"))
      (node (ref "U8") (pin "M13") (pinfunction "DDR_CH1_VDDQ_CK_M13") (pintype "power_in"))
      (node (ref "U8") (pin "N10") (pinfunction "DDR_CH0_VDDQ_1_N10") (pintype "power_in"))
      (node (ref "U8") (pin "P10") (pinfunction "DDR_CH0_VDDQ_2_P10") (pintype "power_in"))
      (node (ref "U8") (pin "R10") (pinfunction "DDR_CH0_VDDQ_3_R10") (pintype "power_in"))
      (node (ref "U8") (pin "T10") (pinfunction "DDR_CH0_VDDQ_4_T10") (pintype "power_in"))
    )
    (net (code "147") (name "VDD_DDR_S0") (class "Default")
      (node (ref "C201") (pin "2") (pinfunction "2_2") (pintype "passive"))
      (node (ref "C202") (pin "2") (pinfunction "2_2") (pintype "passive"))
      (node (ref "C203") (pin "2") (pinfunction "2_2") (pintype "passive"))
      (node (ref "C206") (pin "2") (pinfunction "2_2") (pintype "passive"))
      (node (ref "C207") (pin "2") (pinfunction "2_2") (pintype "passive"))
      (node (ref "C208") (pin "2") (pinfunction "2_2") (pintype "passive"))
      (node (ref "C209") (pin "2") (pinfunction "2_2") (pintype "passive"))
      (node (ref "C210") (pin "2") (pinfunction "2_2") (pintype "passive"))
      (node (ref "C213") (pin "2") (pinfunction "2_2") (pintype "passive"))
      (node (ref "C214") (pin "2") (pinfunction "2_2") (pintype "passive"))
      (node (ref "U8") (pin "L11") (pinfunction "DDR_CH1_VDD_0_L11") (pintype "power_in"))
      (node (ref "U8") (pin "L12") (pinfunction "DDR_CH1_VDD_1_L12") (pintype "power_in"))
      (node (ref "U8") (pin "L13") (pinfunction "DDR_CH1_VDD_2_L13") (pintype "power_in"))
      (node (ref "U8") (pin "L14") (pinfunction "DDR_CH1_VDD_3_L14") (pintype "power_in"))
      (node (ref "U8") (pin "L17") (pinfunction "DDR_CH1_VDD_MIF_0_L17") (pintype "power_in"))
      (node (ref "U8") (pin "L18") (pinfunction "DDR_CH1_VDD_MIF_1_L18") (pintype "power_in"))
      (node (ref "U8") (pin "N13") (pinfunction "DDR_CH0_VDD_MIF_0_N13") (pintype "power_in"))
      (node (ref "U8") (pin "P12") (pinfunction "DDR_CH0_VDD_3_P12") (pintype "power_in"))
      (node (ref "U8") (pin "P13") (pinfunction "DDR_CH0_VDD_MIF_1_P13") (pintype "power_in"))
      (node (ref "U8") (pin "R12") (pinfunction "DDR_CH0_VDD_2_R12") (pintype "power_in"))
      (node (ref "U8") (pin "T12") (pinfunction "DDR_CH0_VDD_1_T12") (pintype "power_in"))
      (node (ref "U8") (pin "U11") (pinfunction "DDR_CH0_VDD_0_U11") (pintype "power_in"))
    )
    (net (code "148") (name "unconnected-(U8A-DDR_CH0_A6_A-PadT5)") (class "Default")
      (node (ref "U8") (pin "T5") (pinfunction "DDR_CH0_A6_A_T5") (pintype "passive+no_connect"))
    )
    (net (code "149") (name "unconnected-(U8A-DDR_CH0_A6_B-PadM7)") (class "Default")
      (node (ref "U8") (pin "M7") (pinfunction "DDR_CH0_A6_B_M7") (pintype "passive+no_connect"))
    )
    (net (code "150") (name "unconnected-(U8A-DDR_CH0_RESET_B-PadK7)") (class "Default")
      (node (ref "U8") (pin "K7") (pinfunction "DDR_CH0_RESET_B_K7") (pintype "passive+no_connect"))
    )
    (net (code "151") (name "unconnected-(U8A-DDR_CH0_WCK0N_A-PadV6)") (class "Default")
      (node (ref "U8") (pin "V6") (pinfunction "DDR_CH0_WCK0N_A_V6") (pintype "passive+no_connect"))
    )
    (net (code "152") (name "unconnected-(U8A-DDR_CH0_WCK0N_B-PadK4)") (class "Default")
      (node (ref "U8") (pin "K4") (pinfunction "DDR_CH0_WCK0N_B_K4") (pintype "passive+no_connect"))
    )
    (net (code "153") (name "unconnected-(U8A-DDR_CH0_WCK0P_A-PadV7)") (class "Default")
      (node (ref "U8") (pin "V7") (pinfunction "DDR_CH0_WCK0P_A_V7") (pintype "passive+no_connect"))
    )
    (net (code "154") (name "unconnected-(U8A-DDR_CH0_WCK0P_B-PadK5)") (class "Default")
      (node (ref "U8") (pin "K5") (pinfunction "DDR_CH0_WCK0P_B_K5") (pintype "passive+no_connect"))
    )
    (net (code "155") (name "unconnected-(U8A-DDR_CH0_WCK1N_A-PadW5)") (class "Default")
      (node (ref "U8") (pin "W5") (pinfunction "DDR_CH0_WCK1N_A_W5") (pintype "passive+no_connect"))
    )
    (net (code "156") (name "unconnected-(U8A-DDR_CH0_WCK1N_B-PadH5)") (class "Default")
      (node (ref "U8") (pin "H5") (pinfunction "DDR_CH0_WCK1N_B_H5") (pintype "passive+no_connect"))
    )
    (net (code "157") (name "unconnected-(U8A-DDR_CH0_WCK1P_A-PadW4)") (class "Default")
      (node (ref "U8") (pin "W4") (pinfunction "DDR_CH0_WCK1P_A_W4") (pintype "passive+no_connect"))
    )
    (net (code "158") (name "unconnected-(U8A-DDR_CH0_WCK1P_B-PadH4)") (class "Default")
      (node (ref "U8") (pin "H4") (pinfunction "DDR_CH0_WCK1P_B_H4") (pintype "passive+no_connect"))
    )
    (net (code "159") (name "unconnected-(U8B-DDR_CH1_A6_C-PadD10)") (class "Default")
      (node (ref "U8") (pin "D10") (pinfunction "DDR_CH1_A6_C_D10") (pintype "passive+no_connect"))
    )
    (net (code "160") (name "unconnected-(U8B-DDR_CH1_A6_D-PadD14)") (class "Default")
      (node (ref "U8") (pin "D14") (pinfunction "DDR_CH1_A6_D_D14") (pintype "passive+no_connect"))
    )
    (net (code "161") (name "unconnected-(U8B-DDR_CH1_RESET_C-PadE10)") (class "Default")
      (node (ref "U8") (pin "E10") (pinfunction "DDR_CH1_RESET_C_E10") (pintype "passive+no_connect"))
    )
    (net (code "162") (name "unconnected-(U8B-DDR_CH1_RESET_D-PadC19)") (class "Default")
      (node (ref "U8") (pin "C19") (pinfunction "DDR_CH1_RESET_D_C19") (pintype "passive+no_connect"))
    )
    (net (code "163") (name "unconnected-(U8B-DDR_CH1_WCK0N_C-PadH9)") (class "Default")
      (node (ref "U8") (pin "H9") (pinfunction "DDR_CH1_WCK0N_C_H9") (pintype "passive+no_connect"))
    )
    (net (code "164") (name "unconnected-(U8B-DDR_CH1_WCK0N_D-PadD17)") (class "Default")
      (node (ref "U8") (pin "D17") (pinfunction "DDR_CH1_WCK0N_D_D17") (pintype "passive+no_connect"))
    )
    (net (code "165") (name "unconnected-(U8B-DDR_CH1_WCK0P_C-PadG9)") (class "Default")
      (node (ref "U8") (pin "G9") (pinfunction "DDR_CH1_WCK0P_C_G9") (pintype "passive+no_connect"))
    )
    (net (code "166") (name "unconnected-(U8B-DDR_CH1_WCK0P_D-PadE17)") (class "Default")
      (node (ref "U8") (pin "E17") (pinfunction "DDR_CH1_WCK0P_D_E17") (pintype "passive+no_connect"))
    )
    (net (code "167") (name "unconnected-(U8B-DDR_CH1_WCK1N_C-PadE7)") (class "Default")
      (node (ref "U8") (pin "E7") (pinfunction "DDR_CH1_WCK1N_C_E7") (pintype "passive+no_connect"))
    )
    (net (code "168") (name "unconnected-(U8B-DDR_CH1_WCK1N_D-PadG18)") (class "Default")
      (node (ref "U8") (pin "G18") (pinfunction "DDR_CH1_WCK1N_D_G18") (pintype "passive+no_connect"))
    )
    (net (code "169") (name "unconnected-(U8B-DDR_CH1_WCK1P_C-PadD7)") (class "Default")
      (node (ref "U8") (pin "D7") (pinfunction "DDR_CH1_WCK1P_C_D7") (pintype "passive+no_connect"))
    )
    (net (code "170") (name "unconnected-(U8B-DDR_CH1_WCK1P_D-PadH18)") (class "Default")
      (node (ref "U8") (pin "H18") (pinfunction "DDR_CH1_WCK1P_D_H18") (pintype "passive+no_connect"))
    )
  )
)
